# WIFI.net
KiCad netlist of a schematic drawn in Altium Designer
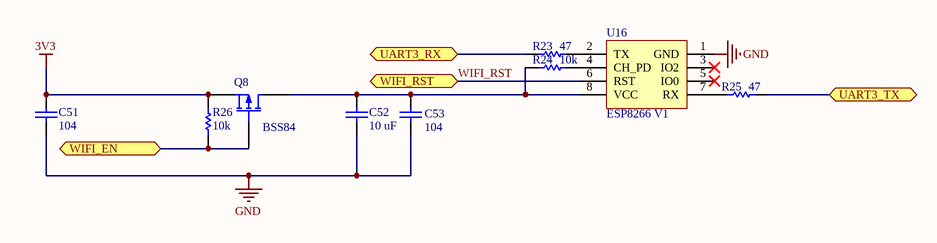
[diagram p0: WIFI.SchDoc]

(export (version "E")
  (design (tool "Eeschema 10.0.6"))
  (components
    (comp (ref "C51")
      (value "104")
      (footprint "C0603")
      (description "CAP CER 0.1UF 16V Y5V 0402")
      (fields
        (field (name "MANUFACTURER") "Yageo")
        (field (name "DIGI-KEY PART NUMBER") "311-1047-1-ND")
        (field (name "PUBLISHER") "Altium Limited")
      )
      (libsource (lib "RobotClub") (part "Cap_SMT"))
    )
    (comp (ref "C52")
      (value "10 uF")
      (footprint "C1210")
      (description "CAP CER 0.1UF 16V Y5V 0402")
      (fields
        (field (name "MANUFACTURER") "Yageo")
        (field (name "DIGI-KEY PART NUMBER") "311-1047-1-ND")
        (field (name "PUBLISHER") "Altium Limited")
      )
      (libsource (lib "RobotClub") (part "Cap_SMT"))
    )
    (comp (ref "C53")
      (value "104")
      (footprint "C0603")
      (description "CAP CER 0.1UF 16V Y5V 0402")
      (fields
        (field (name "MANUFACTURER") "Yageo")
        (field (name "DIGI-KEY PART NUMBER") "311-1047-1-ND")
        (field (name "PUBLISHER") "Altium Limited")
      )
      (libsource (lib "RobotClub") (part "Cap_SMT"))
    )
    (comp (ref "Q8")
      (value "BSS84")
      (footprint "SOT23-3")
      (description "MOSFET P-CH 50V 130MA SOT23-3")
      (fields
        (field (name "DIGI-KEY PART NUMBER") "BSS84-FDITR-ND")
        (field (name "MANUFACTURER") "Diodes Inc")
        (field (name "PUBLISHER") "Altium Limited")
      )
      (libsource (lib "RobotClub") (part "MOSFET-P GSD"))
    )
    (comp (ref "R23")
      (value "47")
      (footprint "R0603")
      (description "Resistor SMD 5%")
      (fields
        (field (name "DIGI-KEY PART NUMBER") "P3.24KLTR-ND")
        (field (name "MANUFACTURER") "Panasonic Electronic Components")
        (field (name "PUBLISHER") "Altium Limited")
      )
      (libsource (lib "RobotClub") (part "R_SMD5"))
    )
    (comp (ref "R24")
      (value "10k")
      (footprint "R0603")
      (description "Resistor SMD 5%")
      (fields
        (field (name "DIGI-KEY PART NUMBER") "P3.24KLTR-ND")
        (field (name "MANUFACTURER") "Panasonic Electronic Components")
        (field (name "PUBLISHER") "Altium Limited")
      )
      (libsource (lib "RobotClub") (part "R_SMD5"))
    )
    (comp (ref "R25")
      (value "47")
      (footprint "R0603")
      (description "Resistor SMD 5%")
      (fields
        (field (name "DIGI-KEY PART NUMBER") "P3.24KLTR-ND")
        (field (name "MANUFACTURER") "Panasonic Electronic Components")
        (field (name "PUBLISHER") "Altium Limited")
      )
      (libsource (lib "RobotClub") (part "R_SMD5"))
    )
    (comp (ref "R26")
      (value "10k")
      (footprint "R0603")
      (description "Resistor SMD 5%")
      (fields
        (field (name "DIGI-KEY PART NUMBER") "P3.24KLTR-ND")
        (field (name "MANUFACTURER") "Panasonic Electronic Components")
        (field (name "PUBLISHER") "Altium Limited")
      )
      (libsource (lib "RobotClub") (part "R_SMD5"))
    )
    (comp (ref "U16")
      (value "ESP8266 V1")
      (footprint "ESP8266 MODULE")
      (fields (field (name "DIGI-KEY PART NUMBER") "NA") (field (name "PUBLISHER") "Altium Limited"))
      (libsource (lib "RobotClub") (part "ESP8266 V1"))
    )
  )
  (nets
    (net (code "1") (name "/UART3_RX") (class "Default")
      (node (ref "R23") (pin "1") (pinfunction "1_1") (pintype "passive"))
    )
    (net (code "2") (name "/UART3_TX") (class "Default")
      (node (ref "R25") (pin "2") (pinfunction "2_2") (pintype "passive"))
    )
    (net (code "3") (name "/WIFI_EN") (class "Default")
      (node (ref "Q8") (pin "1") (pinfunction "G_1") (pintype "passive"))
      (node (ref "R26") (pin "2") (pinfunction "2_2") (pintype "passive"))
    )
    (net (code "4") (name "/WIFI_RST") (class "Default")
      (node (ref "U16") (pin "6") (pinfunction "RST_6") (pintype "passive"))
    )
    (net (code "5") (name "3V3") (class "Default")
      (node (ref "C51") (pin "2") (pinfunction "2_2") (pintype "passive"))
      (node (ref "Q8") (pin "2") (pinfunction "S_2") (pintype "passive"))
      (node (ref "R26") (pin "1") (pinfunction "1_1") (pintype "passive"))
    )
    (net (code "6") (name "GND") (class "Default")
      (node (ref "C51") (pin "1") (pinfunction "1_1") (pintype "passive"))
      (node (ref "C52") (pin "1") (pinfunction "1_1") (pintype "passive"))
      (node (ref "C53") (pin "1") (pinfunction "1_1") (pintype "passive"))
      (node (ref "U16") (pin "1") (pinfunction "GND_1") (pintype "passive"))
    )
    (net (code "7") (name "Net-(Q8-D)") (class "Default")
      (node (ref "C52") (pin "2") (pinfunction "2_2") (pintype "passive"))
      (node (ref "C53") (pin "2") (pinfunction "2_2") (pintype "passive"))
      (node (ref "Q8") (pin "3") (pinfunction "D_3") (pintype "passive"))
      (node (ref "R24") (pin "1") (pinfunction "1_1") (pintype "passive"))
      (node (ref "U16") (pin "8") (pinfunction "VCC_8") (pintype "passive"))
    )
    (net (code "8") (name "Net-(U16-CH_PD)") (class "Default")
      (node (ref "R24") (pin "2") (pinfunction "2_2") (pintype "passive"))
      (node (ref "U16") (pin "4") (pinfunction "CH_PD_4") (pintype "passive"))
    )
    (net (code "9") (name "Net-(U16-RX)") (class "Default")
      (node (ref "R25") (pin "1") (pinfunction "1_1") (pintype "passive"))
      (node (ref "U16") (pin "7") (pinfunction "RX_7") (pintype "passive"))
    )
    (net (code "10") (name "Net-(U16-TX)") (class "Default")
      (node (ref "R23") (pin "2") (pinfunction "2_2") (pintype "passive"))
      (node (ref "U16") (pin "2") (pinfunction "TX_2") (pintype "passive"))
    )
    (net (code "11") (name "unconnected-(U16-IO0-Pad5)") (class "Default")
      (node (ref "U16") (pin "5") (pinfunction "IO0_5") (pintype "passive+no_connect"))
    )
    (net (code "12") (name "unconnected-(U16-IO2-Pad3)") (class "Default")
      (node (ref "U16") (pin "3") (pinfunction "IO2_3") (pintype "passive+no_connect"))
    )
  )
)
